# NSFTC.net
KiCad netlist of a schematic drawn in Altium Designer
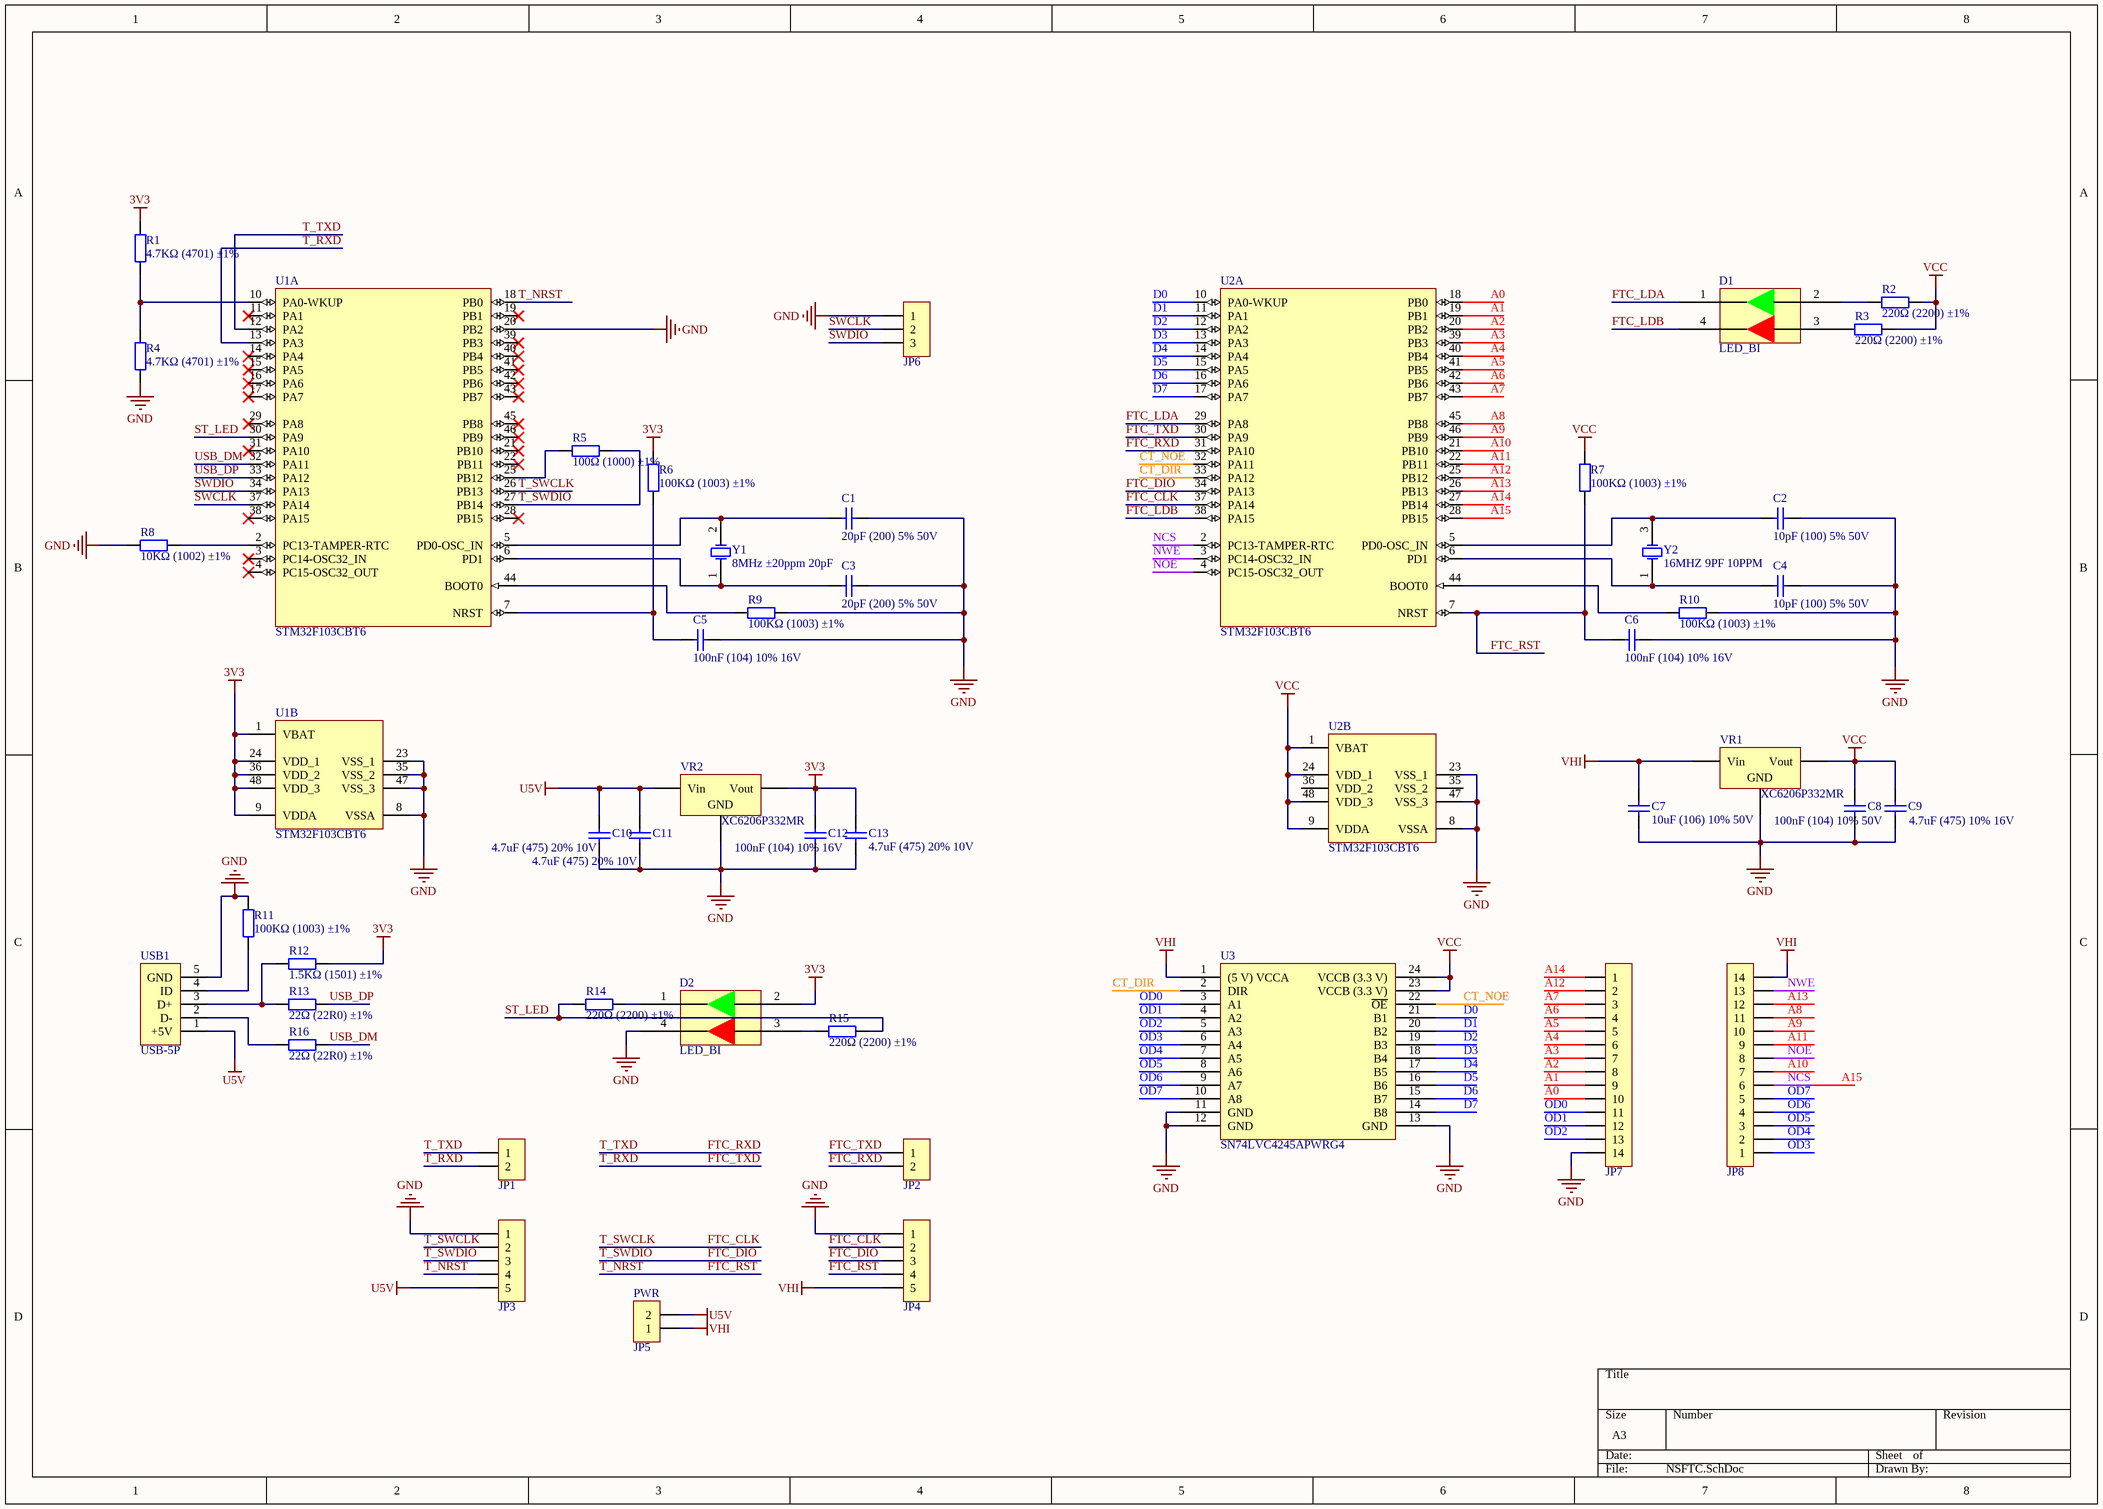
[diagram p0: NSFTC.SchDoc]

(export (version "E")
  (design (tool "Eeschema 10.0.6"))
  (components
    (comp (ref "C1")
      (value "20pF (200) 5% 50V")
      (footprint "0402_C")
      (description "贴片电容")
      (libsource (lib "Miscellaneous Devices LC") (part "0402 20pF (200) 5% 50V"))
    )
    (comp (ref "C2")
      (value "10pF (100) 5% 50V")
      (footprint "0402_C")
      (description "贴片电容")
      (libsource (lib "Miscellaneous Devices LC") (part "0402 10pF (100) 5% 50V"))
    )
    (comp (ref "C3")
      (value "20pF (200) 5% 50V")
      (footprint "0402_C")
      (description "贴片电容")
      (libsource (lib "Miscellaneous Devices LC") (part "0402 20pF (200) 5% 50V"))
    )
    (comp (ref "C4")
      (value "10pF (100) 5% 50V")
      (footprint "0402_C")
      (description "贴片电容")
      (libsource (lib "Miscellaneous Devices LC") (part "0402 10pF (100) 5% 50V"))
    )
    (comp (ref "C5")
      (value "100nF (104) 10% 16V")
      (footprint "0402_C")
      (description "贴片电容")
      (libsource (lib "Miscellaneous Devices LC") (part "0402 100nF (104) 10% 16V"))
    )
    (comp (ref "C6")
      (value "100nF (104) 10% 16V")
      (footprint "0402_C")
      (description "贴片电容")
      (libsource (lib "Miscellaneous Devices LC") (part "0402 100nF (104) 10% 16V"))
    )
    (comp (ref "C7")
      (value "10uF (106) 10% 50V")
      (footprint "1206_C")
      (description "贴片电容")
      (libsource (lib "Miscellaneous Devices LC") (part "1206 10uF (106) 10% 50V"))
    )
    (comp (ref "C8")
      (value "100nF (104) 10% 50V")
      (footprint "0603_C")
      (description "贴片电容")
      (libsource (lib "Miscellaneous Devices LC") (part "0603 100nF (104) 10% 50V"))
    )
    (comp (ref "C9")
      (value "4.7uF (475) 10% 16V")
      (footprint "0603_C")
      (description "贴片电容")
      (libsource (lib "Miscellaneous Devices LC") (part "0603 4.7uF (475) 10% 16V"))
    )
    (comp (ref "C10")
      (value "4.7uF (475) 20% 10V")
      (footprint "0402_C")
      (description "贴片电容")
      (libsource (lib "Miscellaneous Devices LC") (part "0402 4.7uF (475) 20% 10V"))
    )
    (comp (ref "C11")
      (value "4.7uF (475) 20% 10V")
      (footprint "0402_C")
      (description "贴片电容")
      (libsource (lib "Miscellaneous Devices LC") (part "0402 4.7uF (475) 20% 10V"))
    )
    (comp (ref "C12")
      (value "100nF (104) 10% 16V")
      (footprint "0402_C")
      (description "贴片电容")
      (libsource (lib "Miscellaneous Devices LC") (part "0402 100nF (104) 10% 16V"))
    )
    (comp (ref "C13")
      (value "4.7uF (475) 20% 10V")
      (footprint "0402_C")
      (description "贴片电容")
      (libsource (lib "Miscellaneous Devices LC") (part "0402 4.7uF (475) 20% 10V"))
    )
    (comp (ref "D1") (value "LED_BI") (footprint "LED_BI") (libsource (lib "ngh-util") (part "LED_BI")))
    (comp (ref "D2") (value "LED_BI") (footprint "LED_BI") (libsource (lib "ngh-util") (part "LED_BI")))
    (comp (ref "JP1")
      (value "HDR-1X2")
      (footprint "HDR2.54-LI-2P")
      (description "2P接插件")
      (fields (field (name "版权归属") "源创客"))
      (libsource (lib "4.5   - 接插件-脚距2.54") (part "Header 2"))
    )
    (comp (ref "JP2")
      (value "HDR-1X2")
      (footprint "HDR2.54-LI-2P")
      (description "2P接插件")
      (fields (field (name "版权归属") "源创客"))
      (libsource (lib "4.5   - 接插件-脚距2.54") (part "Header 2"))
    )
    (comp (ref "JP3")
      (value "HDR-1X5")
      (footprint "HDR2.54-LI-5P")
      (description "5P接插件")
      (fields (field (name "版权归属") "源创客"))
      (libsource (lib "4.5   - 接插件-脚距2.54") (part "Header 5"))
    )
    (comp (ref "JP4")
      (value "HDR-1X5")
      (footprint "HDR2.54-LI-5P")
      (description "5P接插件")
      (fields (field (name "版权归属") "源创客"))
      (libsource (lib "4.5   - 接插件-脚距2.54") (part "Header 5"))
    )
    (comp (ref "JP5")
      (value "PWR")
      (footprint "HDR2.54-LI-2P")
      (description "2P接插件")
      (fields (field (name "版权归属") "源创客"))
      (libsource (lib "") (part "Header 2_1"))
    )
    (comp (ref "JP6")
      (value "HDR-1X3")
      (footprint "HDR2.54-LI-3P")
      (description "3P接插件")
      (fields (field (name "版权归属") "源创客"))
      (libsource (lib "4.5   - 接插件-脚距2.54") (part "Header 3"))
    )
    (comp (ref "JP7")
      (value "HDR-1X14")
      (footprint "HDR2.54-LI-14P")
      (description "14P接插件")
      (fields (field (name "版权归属") "源创客"))
      (libsource (lib "4.5   - 接插件-脚距2.54") (part "Header 14"))
    )
    (comp (ref "JP8")
      (value "HDR-1X14")
      (footprint "HDR2.54-LI-14P")
      (description "14P接插件")
      (fields (field (name "版权归属") "源创客"))
      (libsource (lib "") (part "Header 14_1"))
    )
    (comp (ref "R1")
      (value "4.7KΩ (4701) ±1%")
      (footprint "0402_R")
      (description "贴片电阻")
      (libsource (lib "Miscellaneous Devices LC") (part "0402 4.7KΩ (4701) 1%"))
    )
    (comp (ref "R2")
      (value "220Ω (2200) ±1%")
      (footprint "0402_R")
      (description "贴片电阻")
      (libsource (lib "Miscellaneous Devices LC") (part "0402 220Ω (2200) 1%"))
    )
    (comp (ref "R3")
      (value "220Ω (2200) ±1%")
      (footprint "0402_R")
      (description "贴片电阻")
      (libsource (lib "Miscellaneous Devices LC") (part "0402 220Ω (2200) 1%"))
    )
    (comp (ref "R4")
      (value "4.7KΩ (4701) ±1%")
      (footprint "0402_R")
      (description "贴片电阻")
      (libsource (lib "Miscellaneous Devices LC") (part "0402 4.7KΩ (4701) 1%"))
    )
    (comp (ref "R5")
      (value "100Ω (1000) ±1%")
      (footprint "0402_R")
      (description "贴片电阻")
      (libsource (lib "Miscellaneous Devices LC") (part "0402 100Ω (1000) 1%"))
    )
    (comp (ref "R6")
      (value "100KΩ (1003) ±1%")
      (footprint "0402_R")
      (description "贴片电阻")
      (libsource (lib "Miscellaneous Devices LC") (part "0402 100KΩ (1003) 1%"))
    )
    (comp (ref "R7")
      (value "100KΩ (1003) ±1%")
      (footprint "0402_R")
      (description "贴片电阻")
      (libsource (lib "Miscellaneous Devices LC") (part "0402 100KΩ (1003) 1%"))
    )
    (comp (ref "R8")
      (value "10KΩ (1002) ±1%")
      (footprint "0402_R")
      (description "贴片电阻")
      (libsource (lib "Miscellaneous Devices LC") (part "0402 10KΩ (1002) 1%"))
    )
    (comp (ref "R9")
      (value "100KΩ (1003) ±1%")
      (footprint "0402_R")
      (description "贴片电阻")
      (libsource (lib "") (part "0402 100KΩ (1003) 1%_1"))
    )
    (comp (ref "R10")
      (value "100KΩ (1003) ±1%")
      (footprint "0402_R")
      (description "贴片电阻")
      (libsource (lib "") (part "0402 100KΩ (1003) 1%_1"))
    )
    (comp (ref "R11")
      (value "100KΩ (1003) ±1%")
      (footprint "0402_R")
      (description "贴片电阻")
      (libsource (lib "Miscellaneous Devices LC") (part "0402 100KΩ (1003) 1%"))
    )
    (comp (ref "R12")
      (value "1.5KΩ (1501) ±1%")
      (footprint "0402_R")
      (description "贴片电阻")
      (libsource (lib "Miscellaneous Devices LC") (part "0402 1.5KΩ (1501) 1%"))
    )
    (comp (ref "R13")
      (value "22Ω (22R0) ±1%")
      (footprint "0402_R")
      (description "贴片电阻")
      (libsource (lib "Miscellaneous Devices LC") (part "0402 22Ω (22R0) 1%"))
    )
    (comp (ref "R14")
      (value "220Ω (2200) ±1%")
      (footprint "0402_R")
      (description "贴片电阻")
      (libsource (lib "Miscellaneous Devices LC") (part "0402 220Ω (2200) 1%"))
    )
    (comp (ref "R15")
      (value "220Ω (2200) ±1%")
      (footprint "0402_R")
      (description "贴片电阻")
      (libsource (lib "Miscellaneous Devices LC") (part "0402 220Ω (2200) 1%"))
    )
    (comp (ref "R16")
      (value "22Ω (22R0) ±1%")
      (footprint "0402_R")
      (description "贴片电阻")
      (libsource (lib "Miscellaneous Devices LC") (part "0402 22Ω (22R0) 1%"))
    )
    (comp (ref "U1")
      (value "STM32F103CBT6")
      (footprint "LQFP-48_7x7x05P")
      (description "ARM")
      (libsource (lib "Miscellaneous Devices LC") (part "STM32F103CBT6"))
    )
    (comp (ref "U2")
      (value "STM32F103CBT6")
      (footprint "LQFP-48_7x7x05P")
      (description "ARM")
      (libsource (lib "Miscellaneous Devices LC") (part "STM32F103CBT6"))
    )
    (comp (ref "U3")
      (value "SN74LVC4245APWRG4")
      (footprint "TSSOP-24")
      (description "74系列逻辑芯片")
      (libsource (lib "Miscellaneous Devices LC") (part "SN74LVC4245APWRG4_[C7859]"))
    )
    (comp (ref "USB1")
      (value "USB-5P")
      (footprint "USB-MICRO_D")
      (description "微型USB母座")
      (fields (field (name "版权归属") "源创客"))
      (libsource (lib "4.1   - 接口类") (part "USB-5P"))
    )
    (comp (ref "VR1")
      (value "XC6206P332MR")
      (footprint "SOT-23-3L")
      (description "低压差线性稳压(LDO)")
      (libsource (lib "Miscellaneous Devices LC") (part "SOT-23 XC6206P332MR"))
    )
    (comp (ref "VR2")
      (value "XC6206P332MR")
      (footprint "SOT-23-3L")
      (description "低压差线性稳压(LDO)")
      (libsource (lib "Miscellaneous Devices LC") (part "SOT-23 XC6206P332MR"))
    )
    (comp (ref "Y1")
      (value "8MHz ±20ppm 20pF")
      (footprint "SMD-5032_2P")
      (description "贴片晶振")
      (libsource (lib "Miscellaneous Devices LC") (part "SMD-5032_2P 8MHz 20ppm 20pF"))
    )
    (comp (ref "Y2")
      (value "16MHZ 9PF 10PPM")
      (footprint "SMD-3225_4P")
      (description "贴片晶振")
      (libsource (lib "Miscellaneous Devices LC") (part "SMD-3225_4P  16MHZ 9PF 10PPM"))
    )
  )
  (nets
    (net (code "1") (name "/A0") (class "Default")
      (node (ref "JP7") (pin "10") (pinfunction "10_10") (pintype "passive"))
      (node (ref "U2") (pin "18") (pinfunction "PB0_18") (pintype "bidirectional"))
    )
    (net (code "2") (name "/A1") (class "Default")
      (node (ref "JP7") (pin "9") (pinfunction "9_9") (pintype "passive"))
      (node (ref "U2") (pin "19") (pinfunction "PB1_19") (pintype "bidirectional"))
    )
    (net (code "3") (name "/A2") (class "Default")
      (node (ref "JP7") (pin "8") (pinfunction "8_8") (pintype "passive"))
      (node (ref "U2") (pin "20") (pinfunction "PB2_20") (pintype "bidirectional"))
    )
    (net (code "4") (name "/A3") (class "Default")
      (node (ref "JP7") (pin "7") (pinfunction "7_7") (pintype "passive"))
      (node (ref "U2") (pin "39") (pinfunction "PB3_39") (pintype "bidirectional"))
    )
    (net (code "5") (name "/A4") (class "Default")
      (node (ref "JP7") (pin "6") (pinfunction "6_6") (pintype "passive"))
      (node (ref "U2") (pin "40") (pinfunction "PB4_40") (pintype "bidirectional"))
    )
    (net (code "6") (name "/A5") (class "Default")
      (node (ref "JP7") (pin "5") (pinfunction "5_5") (pintype "passive"))
      (node (ref "U2") (pin "41") (pinfunction "PB5_41") (pintype "bidirectional"))
    )
    (net (code "7") (name "/A6") (class "Default")
      (node (ref "JP7") (pin "4") (pinfunction "4_4") (pintype "passive"))
      (node (ref "U2") (pin "42") (pinfunction "PB6_42") (pintype "bidirectional"))
    )
    (net (code "8") (name "/A7") (class "Default")
      (node (ref "JP7") (pin "3") (pinfunction "3_3") (pintype "passive"))
      (node (ref "U2") (pin "43") (pinfunction "PB7_43") (pintype "bidirectional"))
    )
    (net (code "9") (name "/A8") (class "Default")
      (node (ref "JP8") (pin "11") (pinfunction "11_11") (pintype "passive"))
      (node (ref "U2") (pin "45") (pinfunction "PB8_45") (pintype "bidirectional"))
    )
    (net (code "10") (name "/A9") (class "Default")
      (node (ref "JP8") (pin "10") (pinfunction "10_10") (pintype "passive"))
      (node (ref "U2") (pin "46") (pinfunction "PB9_46") (pintype "bidirectional"))
    )
    (net (code "11") (name "/A10") (class "Default")
      (node (ref "JP8") (pin "7") (pinfunction "7_7") (pintype "passive"))
      (node (ref "U2") (pin "21") (pinfunction "PB10_21") (pintype "bidirectional"))
    )
    (net (code "12") (name "/A11") (class "Default")
      (node (ref "JP8") (pin "9") (pinfunction "9_9") (pintype "passive"))
      (node (ref "U2") (pin "22") (pinfunction "PB11_22") (pintype "bidirectional"))
    )
    (net (code "13") (name "/A12") (class "Default")
      (node (ref "JP7") (pin "2") (pinfunction "2_2") (pintype "passive"))
      (node (ref "U2") (pin "25") (pinfunction "PB12_25") (pintype "bidirectional"))
    )
    (net (code "14") (name "/A13") (class "Default")
      (node (ref "JP8") (pin "12") (pinfunction "12_12") (pintype "passive"))
      (node (ref "U2") (pin "26") (pinfunction "PB13_26") (pintype "bidirectional"))
    )
    (net (code "15") (name "/A14") (class "Default")
      (node (ref "JP7") (pin "1") (pinfunction "1_1") (pintype "passive"))
      (node (ref "U2") (pin "27") (pinfunction "PB14_27") (pintype "bidirectional"))
    )
    (net (code "16") (name "/A15") (class "Default")
      (node (ref "JP8") (pin "6") (pinfunction "6_6") (pintype "passive"))
      (node (ref "U2") (pin "2") (pinfunction "PC13-TAMPER-RTC_2") (pintype "bidirectional"))
      (node (ref "U2") (pin "28") (pinfunction "PB15_28") (pintype "bidirectional"))
    )
    (net (code "17") (name "/CT_DIR") (class "Default")
      (node (ref "U2") (pin "33") (pinfunction "PA12_33") (pintype "bidirectional"))
      (node (ref "U3") (pin "2") (pinfunction "DIR_2") (pintype "passive"))
    )
    (net (code "18") (name "/CT_NOE") (class "Default")
      (node (ref "U2") (pin "32") (pinfunction "PA11_32") (pintype "bidirectional"))
      (node (ref "U3") (pin "22") (pinfunction "~{OE}_22") (pintype "passive"))
    )
    (net (code "19") (name "/D0") (class "Default")
      (node (ref "U2") (pin "10") (pinfunction "PA0-WKUP_10") (pintype "bidirectional"))
      (node (ref "U3") (pin "21") (pinfunction "B1_21") (pintype "passive"))
    )
    (net (code "20") (name "/D1") (class "Default")
      (node (ref "U2") (pin "11") (pinfunction "PA1_11") (pintype "bidirectional"))
      (node (ref "U3") (pin "20") (pinfunction "B2_20") (pintype "passive"))
    )
    (net (code "21") (name "/D2") (class "Default")
      (node (ref "U2") (pin "12") (pinfunction "PA2_12") (pintype "bidirectional"))
      (node (ref "U3") (pin "19") (pinfunction "B3_19") (pintype "passive"))
    )
    (net (code "22") (name "/D3") (class "Default")
      (node (ref "U2") (pin "13") (pinfunction "PA3_13") (pintype "bidirectional"))
      (node (ref "U3") (pin "18") (pinfunction "B4_18") (pintype "passive"))
    )
    (net (code "23") (name "/D4") (class "Default")
      (node (ref "U2") (pin "14") (pinfunction "PA4_14") (pintype "bidirectional"))
      (node (ref "U3") (pin "17") (pinfunction "B5_17") (pintype "passive"))
    )
    (net (code "24") (name "/D5") (class "Default")
      (node (ref "U2") (pin "15") (pinfunction "PA5_15") (pintype "bidirectional"))
      (node (ref "U3") (pin "16") (pinfunction "B6_16") (pintype "passive"))
    )
    (net (code "25") (name "/D6") (class "Default")
      (node (ref "U2") (pin "16") (pinfunction "PA6_16") (pintype "bidirectional"))
      (node (ref "U3") (pin "15") (pinfunction "B7_15") (pintype "passive"))
    )
    (net (code "26") (name "/D7") (class "Default")
      (node (ref "U2") (pin "17") (pinfunction "PA7_17") (pintype "bidirectional"))
      (node (ref "U3") (pin "14") (pinfunction "B8_14") (pintype "passive"))
    )
    (net (code "27") (name "/FTC_CLK") (class "Default")
      (node (ref "JP3") (pin "2") (pinfunction "2_2") (pintype "passive"))
      (node (ref "JP4") (pin "2") (pinfunction "2_2") (pintype "passive"))
      (node (ref "U1") (pin "26") (pinfunction "PB13_26") (pintype "bidirectional"))
      (node (ref "U2") (pin "37") (pinfunction "PA14_37") (pintype "bidirectional"))
    )
    (net (code "28") (name "/FTC_DIO") (class "Default")
      (node (ref "JP3") (pin "3") (pinfunction "3_3") (pintype "passive"))
      (node (ref "JP4") (pin "3") (pinfunction "3_3") (pintype "passive"))
      (node (ref "R5") (pin "2") (pinfunction "2_2") (pintype "passive"))
      (node (ref "U1") (pin "27") (pinfunction "PB14_27") (pintype "bidirectional"))
      (node (ref "U2") (pin "34") (pinfunction "PA13_34") (pintype "bidirectional"))
    )
    (net (code "29") (name "/FTC_LDA") (class "Default")
      (node (ref "D1") (pin "1") (pinfunction "1_1") (pintype "passive"))
      (node (ref "U2") (pin "29") (pinfunction "PA8_29") (pintype "bidirectional"))
    )
    (net (code "30") (name "/FTC_LDB") (class "Default")
      (node (ref "D1") (pin "4") (pinfunction "4_4") (pintype "passive"))
      (node (ref "U2") (pin "38") (pinfunction "PA15_38") (pintype "bidirectional"))
    )
    (net (code "31") (name "/FTC_RST") (class "Default")
      (node (ref "C6") (pin "2") (pinfunction "2_2") (pintype "passive"))
      (node (ref "JP3") (pin "4") (pinfunction "4_4") (pintype "passive"))
      (node (ref "JP4") (pin "4") (pinfunction "4_4") (pintype "passive"))
      (node (ref "R7") (pin "1") (pinfunction "1_1") (pintype "passive"))
      (node (ref "U1") (pin "18") (pinfunction "PB0_18") (pintype "bidirectional"))
      (node (ref "U2") (pin "7") (pinfunction "NRST_7") (pintype "bidirectional"))
    )
    (net (code "32") (name "/FTC_RXD") (class "Default")
      (node (ref "JP1") (pin "1") (pinfunction "1_1") (pintype "passive"))
      (node (ref "JP2") (pin "2") (pinfunction "2_2") (pintype "passive"))
      (node (ref "U1") (pin "12") (pinfunction "PA2_12") (pintype "bidirectional"))
      (node (ref "U2") (pin "31") (pinfunction "PA10_31") (pintype "bidirectional"))
    )
    (net (code "33") (name "/FTC_TXD") (class "Default")
      (node (ref "JP1") (pin "2") (pinfunction "2_2") (pintype "passive"))
      (node (ref "JP2") (pin "1") (pinfunction "1_1") (pintype "passive"))
      (node (ref "U1") (pin "13") (pinfunction "PA3_13") (pintype "bidirectional"))
      (node (ref "U2") (pin "30") (pinfunction "PA9_30") (pintype "bidirectional"))
    )
    (net (code "34") (name "/NOE") (class "Default")
      (node (ref "JP8") (pin "8") (pinfunction "8_8") (pintype "passive"))
      (node (ref "U2") (pin "4") (pinfunction "PC15-OSC32_OUT_4") (pintype "bidirectional"))
    )
    (net (code "35") (name "/NWE") (class "Default")
      (node (ref "JP8") (pin "13") (pinfunction "13_13") (pintype "passive"))
      (node (ref "U2") (pin "3") (pinfunction "PC14-OSC32_IN_3") (pintype "bidirectional"))
    )
    (net (code "36") (name "/OD0") (class "Default")
      (node (ref "JP7") (pin "11") (pinfunction "11_11") (pintype "passive"))
      (node (ref "U3") (pin "3") (pinfunction "A1_3") (pintype "passive"))
    )
    (net (code "37") (name "/OD1") (class "Default")
      (node (ref "JP7") (pin "12") (pinfunction "12_12") (pintype "passive"))
      (node (ref "U3") (pin "4") (pinfunction "A2_4") (pintype "passive"))
    )
    (net (code "38") (name "/OD2") (class "Default")
      (node (ref "JP7") (pin "13") (pinfunction "13_13") (pintype "passive"))
      (node (ref "U3") (pin "5") (pinfunction "A3_5") (pintype "passive"))
    )
    (net (code "39") (name "/OD3") (class "Default")
      (node (ref "JP8") (pin "1") (pinfunction "1_1") (pintype "passive"))
      (node (ref "U3") (pin "6") (pinfunction "A4_6") (pintype "passive"))
    )
    (net (code "40") (name "/OD4") (class "Default")
      (node (ref "JP8") (pin "2") (pinfunction "2_2") (pintype "passive"))
      (node (ref "U3") (pin "7") (pinfunction "A5_7") (pintype "passive"))
    )
    (net (code "41") (name "/OD5") (class "Default")
      (node (ref "JP8") (pin "3") (pinfunction "3_3") (pintype "passive"))
      (node (ref "U3") (pin "8") (pinfunction "A6_8") (pintype "passive"))
    )
    (net (code "42") (name "/OD6") (class "Default")
      (node (ref "JP8") (pin "4") (pinfunction "4_4") (pintype "passive"))
      (node (ref "U3") (pin "9") (pinfunction "A7_9") (pintype "passive"))
    )
    (net (code "43") (name "/OD7") (class "Default")
      (node (ref "JP8") (pin "5") (pinfunction "5_5") (pintype "passive"))
      (node (ref "U3") (pin "10") (pinfunction "A8_10") (pintype "passive"))
    )
    (net (code "44") (name "/ST_LED") (class "Default")
      (node (ref "R14") (pin "1") (pinfunction "1_1") (pintype "passive"))
      (node (ref "R15") (pin "2") (pinfunction "2_2") (pintype "passive"))
      (node (ref "U1") (pin "30") (pinfunction "PA9_30") (pintype "bidirectional"))
    )
    (net (code "45") (name "/SWCLK") (class "Default")
      (node (ref "JP6") (pin "2") (pinfunction "2_2") (pintype "passive"))
      (node (ref "U1") (pin "37") (pinfunction "PA14_37") (pintype "bidirectional"))
    )
    (net (code "46") (name "/SWDIO") (class "Default")
      (node (ref "JP6") (pin "3") (pinfunction "3_3") (pintype "passive"))
      (node (ref "U1") (pin "34") (pinfunction "PA13_34") (pintype "bidirectional"))
    )
    (net (code "47") (name "/USB_DM") (class "Default")
      (node (ref "R16") (pin "2") (pinfunction "2_2") (pintype "passive"))
      (node (ref "U1") (pin "32") (pinfunction "PA11_32") (pintype "bidirectional"))
    )
    (net (code "48") (name "/USB_DP") (class "Default")
      (node (ref "R13") (pin "2") (pinfunction "2_2") (pintype "passive"))
      (node (ref "U1") (pin "33") (pinfunction "PA12_33") (pintype "bidirectional"))
    )
    (net (code "49") (name "3V3") (class "Default")
      (node (ref "C12") (pin "2") (pinfunction "2_2") (pintype "passive"))
      (node (ref "C13") (pin "2") (pinfunction "2_2") (pintype "passive"))
      (node (ref "D2") (pin "2") (pinfunction "2_2") (pintype "passive"))
      (node (ref "R1") (pin "2") (pinfunction "2_2") (pintype "passive"))
      (node (ref "R12") (pin "2") (pinfunction "2_2") (pintype "passive"))
      (node (ref "R6") (pin "2") (pinfunction "2_2") (pintype "passive"))
      (node (ref "U1") (pin "1") (pinfunction "VBAT_1") (pintype "power_in"))
      (node (ref "U1") (pin "24") (pinfunction "VDD_1_24") (pintype "power_in"))
      (node (ref "U1") (pin "36") (pinfunction "VDD_2_36") (pintype "power_in"))
      (node (ref "U1") (pin "48") (pinfunction "VDD_3_48") (pintype "power_in"))
      (node (ref "U1") (pin "9") (pinfunction "VDDA_9") (pintype "power_in"))
      (node (ref "VR2") (pin "2") (pinfunction "Vout_2") (pintype "passive"))
    )
    (net (code "50") (name "GND") (class "Default")
      (node (ref "C1") (pin "2") (pinfunction "2_2") (pintype "passive"))
      (node (ref "C10") (pin "1") (pinfunction "1_1") (pintype "passive"))
      (node (ref "C11") (pin "1") (pinfunction "1_1") (pintype "passive"))
      (node (ref "C12") (pin "1") (pinfunction "1_1") (pintype "passive"))
      (node (ref "C13") (pin "1") (pinfunction "1_1") (pintype "passive"))
      (node (ref "C2") (pin "2") (pinfunction "2_2") (pintype "passive"))
      (node (ref "C3") (pin "2") (pinfunction "2_2") (pintype "passive"))
      (node (ref "C4") (pin "2") (pinfunction "2_2") (pintype "passive"))
      (node (ref "C5") (pin "1") (pinfunction "1_1") (pintype "passive"))
      (node (ref "C6") (pin "1") (pinfunction "1_1") (pintype "passive"))
      (node (ref "C7") (pin "1") (pinfunction "1_1") (pintype "passive"))
      (node (ref "C8") (pin "1") (pinfunction "1_1") (pintype "passive"))
      (node (ref "C9") (pin "1") (pinfunction "1_1") (pintype "passive"))
      (node (ref "D2") (pin "4") (pinfunction "4_4") (pintype "passive"))
      (node (ref "JP3") (pin "1") (pinfunction "1_1") (pintype "passive"))
      (node (ref "JP4") (pin "1") (pinfunction "1_1") (pintype "passive"))
      (node (ref "JP6") (pin "1") (pinfunction "1_1") (pintype "passive"))
      (node (ref "JP7") (pin "14") (pinfunction "14_14") (pintype "passive"))
      (node (ref "R10") (pin "2") (pinfunction "2_2") (pintype "passive"))
      (node (ref "R11") (pin "2") (pinfunction "2_2") (pintype "passive"))
      (node (ref "R4") (pin "1") (pinfunction "1_1") (pintype "passive"))
      (node (ref "R8") (pin "1") (pinfunction "1_1") (pintype "passive"))
      (node (ref "R9") (pin "2") (pinfunction "2_2") (pintype "passive"))
      (node (ref "U1") (pin "20") (pinfunction "PB2_20") (pintype "bidirectional"))
      (node (ref "U1") (pin "23") (pinfunction "VSS_1_23") (pintype "power_in"))
      (node (ref "U1") (pin "35") (pinfunction "VSS_2_35") (pintype "power_in"))
      (node (ref "U1") (pin "47") (pinfunction "VSS_3_47") (pintype "power_in"))
      (node (ref "U1") (pin "8") (pinfunction "VSSA_8") (pintype "power_in"))
      (node (ref "U2") (pin "23") (pinfunction "VSS_1_23") (pintype "power_in"))
      (node (ref "U2") (pin "47") (pinfunction "VSS_3_47") (pintype "power_in"))
      (node (ref "U2") (pin "8") (pinfunction "VSSA_8") (pintype "power_in"))
      (node (ref "U3") (pin "11") (pinfunction "GND_11") (pintype "passive"))
      (node (ref "U3") (pin "12") (pinfunction "GND_12") (pintype "passive"))
      (node (ref "U3") (pin "13") (pinfunction "GND_13") (pintype "passive"))
      (node (ref "USB1") (pin "5") (pinfunction "GND_5") (pintype "passive"))
      (node (ref "VR1") (pin "1") (pinfunction "GND_1") (pintype "passive"))
      (node (ref "VR2") (pin "1") (pinfunction "GND_1") (pintype "passive"))
    )
    (net (code "51") (name "Net-(D1-Pad2)") (class "Default")
      (node (ref "D1") (pin "2") (pinfunction "2_2") (pintype "passive"))
      (node (ref "R2") (pin "1") (pinfunction "1_1") (pintype "passive"))
    )
    (net (code "52") (name "Net-(D1-Pad3)") (class "Default")
      (node (ref "D1") (pin "3") (pinfunction "3_3") (pintype "passive"))
      (node (ref "R3") (pin "1") (pinfunction "1_1") (pintype "passive"))
    )
    (net (code "53") (name "Net-(D2-Pad1)") (class "Default")
      (node (ref "D2") (pin "1") (pinfunction "1_1") (pintype "passive"))
      (node (ref "R14") (pin "2") (pinfunction "2_2") (pintype "passive"))
    )
    (net (code "54") (name "Net-(D2-Pad3)") (class "Default")
      (node (ref "D2") (pin "3") (pinfunction "3_3") (pintype "passive"))
      (node (ref "R15") (pin "1") (pinfunction "1_1") (pintype "passive"))
    )
    (net (code "55") (name "Net-(U1A-BOOT0)") (class "Default")
      (node (ref "R9") (pin "1") (pinfunction "1_1") (pintype "passive"))
      (node (ref "U1") (pin "44") (pinfunction "BOOT0_44") (pintype "input"))
    )
    (net (code "56") (name "Net-(U1A-NRST)") (class "Default")
      (node (ref "C5") (pin "2") (pinfunction "2_2") (pintype "passive"))
      (node (ref "R6") (pin "1") (pinfunction "1_1") (pintype "passive"))
      (node (ref "U1") (pin "7") (pinfunction "NRST_7") (pintype "bidirectional"))
    )
    (net (code "57") (name "Net-(U1A-PA0-WKUP)") (class "Default")
      (node (ref "R1") (pin "1") (pinfunction "1_1") (pintype "passive"))
      (node (ref "R4") (pin "2") (pinfunction "2_2") (pintype "passive"))
      (node (ref "U1") (pin "10") (pinfunction "PA0-WKUP_10") (pintype "bidirectional"))
    )
    (net (code "58") (name "Net-(U1A-PB12)") (class "Default")
      (node (ref "R5") (pin "1") (pinfunction "1_1") (pintype "passive"))
      (node (ref "U1") (pin "25") (pinfunction "PB12_25") (pintype "bidirectional"))
    )
    (net (code "59") (name "Net-(U1A-PC13-TAMPER-RTC)") (class "Default")
      (node (ref "R8") (pin "2") (pinfunction "2_2") (pintype "passive"))
      (node (ref "U1") (pin "2") (pinfunction "PC13-TAMPER-RTC_2") (pintype "bidirectional"))
    )
    (net (code "60") (name "Net-(U1A-PD0-OSC_IN)") (class "Default")
      (node (ref "C1") (pin "1") (pinfunction "1_1") (pintype "passive"))
      (node (ref "U1") (pin "5") (pinfunction "PD0-OSC_IN_5") (pintype "bidirectional"))
      (node (ref "Y1") (pin "2") (pinfunction "OSC2_2") (pintype "passive"))
    )
    (net (code "61") (name "Net-(U1A-PD1)") (class "Default")
      (node (ref "C3") (pin "1") (pinfunction "1_1") (pintype "passive"))
      (node (ref "U1") (pin "6") (pinfunction "PD1_6") (pintype "bidirectional"))
      (node (ref "Y1") (pin "1") (pinfunction "OSC1_1") (pintype "passive"))
    )
    (net (code "62") (name "Net-(U2A-BOOT0)") (class "Default")
      (node (ref "R10") (pin "1") (pinfunction "1_1") (pintype "passive"))
      (node (ref "U2") (pin "44") (pinfunction "BOOT0_44") (pintype "input"))
    )
    (net (code "63") (name "Net-(U2A-PD0-OSC_IN)") (class "Default")
      (node (ref "C2") (pin "1") (pinfunction "1_1") (pintype "passive"))
      (node (ref "U2") (pin "5") (pinfunction "PD0-OSC_IN_5") (pintype "bidirectional"))
      (node (ref "Y2") (pin "3") (pinfunction "OSC2_3") (pintype "passive"))
    )
    (net (code "64") (name "Net-(U2A-PD1)") (class "Default")
      (node (ref "C4") (pin "1") (pinfunction "1_1") (pintype "passive"))
      (node (ref "U2") (pin "6") (pinfunction "PD1_6") (pintype "bidirectional"))
      (node (ref "Y2") (pin "1") (pinfunction "OSC1_1") (pintype "passive"))
    )
    (net (code "65") (name "Net-(USB1-D+)") (class "Default")
      (node (ref "R12") (pin "1") (pinfunction "1_1") (pintype "passive"))
      (node (ref "R13") (pin "1") (pinfunction "1_1") (pintype "passive"))
      (node (ref "USB1") (pin "3") (pinfunction "D+_3") (pintype "passive"))
    )
    (net (code "66") (name "Net-(USB1-D-)") (class "Default")
      (node (ref "R16") (pin "1") (pinfunction "1_1") (pintype "passive"))
      (node (ref "USB1") (pin "2") (pinfunction "D-_2") (pintype "passive"))
    )
    (net (code "67") (name "Net-(USB1-ID)") (class "Default")
      (node (ref "R11") (pin "1") (pinfunction "1_1") (pintype "passive"))
      (node (ref "USB1") (pin "4") (pinfunction "ID_4") (pintype "passive"))
    )
    (net (code "68") (name "U5V") (class "Default")
      (node (ref "C10") (pin "2") (pinfunction "2_2") (pintype "passive"))
      (node (ref "C11") (pin "2") (pinfunction "2_2") (pintype "passive"))
      (node (ref "JP3") (pin "5") (pinfunction "5_5") (pintype "passive"))
      (node (ref "JP5") (pin "2") (pinfunction "2_2") (pintype "passive"))
      (node (ref "USB1") (pin "1") (pinfunction "+5V_1") (pintype "passive"))
      (node (ref "VR2") (pin "3") (pinfunction "Vin_3") (pintype "passive"))
    )
    (net (code "69") (name "VCC") (class "Default")
      (node (ref "C8") (pin "2") (pinfunction "2_2") (pintype "passive"))
      (node (ref "C9") (pin "2") (pinfunction "2_2") (pintype "passive"))
      (node (ref "R2") (pin "2") (pinfunction "2_2") (pintype "passive"))
      (node (ref "R3") (pin "2") (pinfunction "2_2") (pintype "passive"))
      (node (ref "R7") (pin "2") (pinfunction "2_2") (pintype "passive"))
      (node (ref "U2") (pin "1") (pinfunction "VBAT_1") (pintype "power_in"))
      (node (ref "U2") (pin "24") (pinfunction "VDD_1_24") (pintype "power_in"))
      (node (ref "U2") (pin "48") (pinfunction "VDD_3_48") (pintype "power_in"))
      (node (ref "U2") (pin "9") (pinfunction "VDDA_9") (pintype "power_in"))
      (node (ref "U3") (pin "23") (pinfunction "VCCB_(3.3_V)_23") (pintype "passive"))
      (node (ref "U3") (pin "24") (pinfunction "VCCB_(3.3_V)_24") (pintype "passive"))
      (node (ref "VR1") (pin "2") (pinfunction "Vout_2") (pintype "passive"))
    )
    (net (code "70") (name "VHI") (class "Default")
      (node (ref "C7") (pin "2") (pinfunction "2_2") (pintype "passive"))
      (node (ref "JP4") (pin "5") (pinfunction "5_5") (pintype "passive"))
      (node (ref "JP5") (pin "1") (pinfunction "1_1") (pintype "passive"))
      (node (ref "JP8") (pin "14") (pinfunction "14_14") (pintype "passive"))
      (node (ref "U3") (pin "1") (pinfunction "(5_V)_VCCA_1") (pintype "passive"))
      (node (ref "VR1") (pin "3") (pinfunction "Vin_3") (pintype "passive"))
    )
    (net (code "71") (name "unconnected-(U1A-PA1-Pad11)") (class "Default")
      (node (ref "U1") (pin "11") (pinfunction "PA1_11") (pintype "bidirectional+no_connect"))
    )
    (net (code "72") (name "unconnected-(U1A-PA4-Pad14)") (class "Default")
      (node (ref "U1") (pin "14") (pinfunction "PA4_14") (pintype "bidirectional+no_connect"))
    )
    (net (code "73") (name "unconnected-(U1A-PA5-Pad15)") (class "Default")
      (node (ref "U1") (pin "15") (pinfunction "PA5_15") (pintype "bidirectional+no_connect"))
    )
    (net (code "74") (name "unconnected-(U1A-PA6-Pad16)") (class "Default")
      (node (ref "U1") (pin "16") (pinfunction "PA6_16") (pintype "bidirectional+no_connect"))
    )
    (net (code "75") (name "unconnected-(U1A-PA7-Pad17)") (class "Default")
      (node (ref "U1") (pin "17") (pinfunction "PA7_17") (pintype "bidirectional+no_connect"))
    )
    (net (code "76") (name "unconnected-(U1A-PA8-Pad29)") (class "Default")
      (node (ref "U1") (pin "29") (pinfunction "PA8_29") (pintype "bidirectional+no_connect"))
    )
    (net (code "77") (name "unconnected-(U1A-PA10-Pad31)") (class "Default")
      (node (ref "U1") (pin "31") (pinfunction "PA10_31") (pintype "bidirectional+no_connect"))
    )
    (net (code "78") (name "unconnected-(U1A-PA15-Pad38)") (class "Default")
      (node (ref "U1") (pin "38") (pinfunction "PA15_38") (pintype "bidirectional+no_connect"))
    )
    (net (code "79") (name "unconnected-(U1A-PB1-Pad19)") (class "Default")
      (node (ref "U1") (pin "19") (pinfunction "PB1_19") (pintype "bidirectional+no_connect"))
    )
    (net (code "80") (name "unconnected-(U1A-PB3-Pad39)") (class "Default")
      (node (ref "U1") (pin "39") (pinfunction "PB3_39") (pintype "bidirectional+no_connect"))
    )
    (net (code "81") (name "unconnected-(U1A-PB4-Pad40)") (class "Default")
      (node (ref "U1") (pin "40") (pinfunction "PB4_40") (pintype "bidirectional+no_connect"))
    )
    (net (code "82") (name "unconnected-(U1A-PB5-Pad41)") (class "Default")
      (node (ref "U1") (pin "41") (pinfunction "PB5_41") (pintype "bidirectional+no_connect"))
    )
    (net (code "83") (name "unconnected-(U1A-PB6-Pad42)") (class "Default")
      (node (ref "U1") (pin "42") (pinfunction "PB6_42") (pintype "bidirectional+no_connect"))
    )
    (net (code "84") (name "unconnected-(U1A-PB7-Pad43)") (class "Default")
      (node (ref "U1") (pin "43") (pinfunction "PB7_43") (pintype "bidirectional+no_connect"))
    )
    (net (code "85") (name "unconnected-(U1A-PB8-Pad45)") (class "Default")
      (node (ref "U1") (pin "45") (pinfunction "PB8_45") (pintype "bidirectional+no_connect"))
    )
    (net (code "86") (name "unconnected-(U1A-PB9-Pad46)") (class "Default")
      (node (ref "U1") (pin "46") (pinfunction "PB9_46") (pintype "bidirectional+no_connect"))
    )
    (net (code "87") (name "unconnected-(U1A-PB10-Pad21)") (class "Default")
      (node (ref "U1") (pin "21") (pinfunction "PB10_21") (pintype "bidirectional+no_connect"))
    )
    (net (code "88") (name "unconnected-(U1A-PB11-Pad22)") (class "Default")
      (node (ref "U1") (pin "22") (pinfunction "PB11_22") (pintype "bidirectional+no_connect"))
    )
    (net (code "89") (name "unconnected-(U1A-PB15-Pad28)") (class "Default")
      (node (ref "U1") (pin "28") (pinfunction "PB15_28") (pintype "bidirectional+no_connect"))
    )
    (net (code "90") (name "unconnected-(U1A-PC14-OSC32_IN-Pad3)") (class "Default")
      (node (ref "U1") (pin "3") (pinfunction "PC14-OSC32_IN_3") (pintype "bidirectional+no_connect"))
    )
    (net (code "91") (name "unconnected-(U1A-PC15-OSC32_OUT-Pad4)") (class "Default")
      (node (ref "U1") (pin "4") (pinfunction "PC15-OSC32_OUT_4") (pintype "bidirectional+no_connect"))
    )
    (net (code "92") (name "unconnected-(U2B-VDD_2-Pad36)") (class "Default")
      (node (ref "U2") (pin "36") (pinfunction "VDD_2_36") (pintype "power_in"))
    )
    (net (code "93") (name "unconnected-(U2B-VSS_2-Pad35)") (class "Default")
      (node (ref "U2") (pin "35") (pinfunction "VSS_2_35") (pintype "power_in"))
    )
  )
)
